# Sheet1.net
KiCad netlist of a schematic drawn in Altium Designer
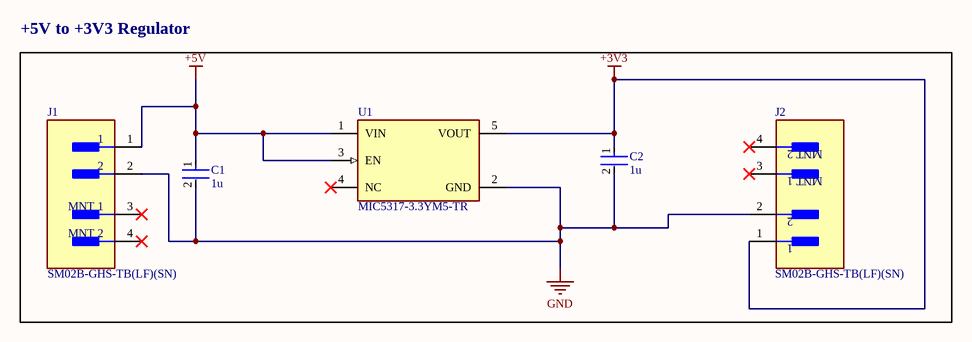
[diagram p0: Sheet1.SchDoc]

(export (version "E")
  (design (tool "Eeschema 10.0.6"))
  (components
    (comp (ref "C1")
      (value "1u")
      (footprint "FP-CC0805-0_85-MFG")
      (description "CAP CER 1UF 10V X7R 0805")
      (fields
        (field (name "MANUFACTURER") "Yageo")
        (field (name "OCTOPART") "https://octopart.com/cc0805kkx7r6bb105-yageo-42522859")
      )
      (libsource (lib "Altium Content Vault") (part "11868f565c42a9108669ba33697ecf6"))
    )
    (comp (ref "C2")
      (value "1u")
      (footprint "FP-CC0805-0_85-MFG")
      (description "CAP CER 1UF 10V X7R 0805")
      (fields
        (field (name "MANUFACTURER") "Yageo")
        (field (name "OCTOPART") "https://octopart.com/cc0805kkx7r6bb105-yageo-42522859")
      )
      (libsource (lib "Altium Content Vault") (part "11868f565c42a9108669ba33697ecf6"))
    )
    (comp (ref "J1")
      (value "SM02B-GHS-TB(LF)(SN)")
      (footprint "FP-SM02B-GHS-TB_LF_SN-MFG")
      (description "CONN HEADER SMD R/A 2POS 1.25MM")
      (libsource (lib "Altium Content Vault") (part "56ec3178a87b3978bdc1b3682cd516a"))
    )
    (comp (ref "J2")
      (value "SM02B-GHS-TB(LF)(SN)")
      (footprint "FP-SM02B-GHS-TB_LF_SN-MFG")
      (description "CONN HEADER SMD R/A 2POS 1.25MM")
      (libsource (lib "") (part "56ec3178a87b3978bdc1b3682cd516a_1"))
    )
    (comp (ref "U1")
      (value "MIC5317-3.3YM5-TR")
      (footprint "FP-SOT23-5LD-PL-1-MFG")
      (description "IC REG LINEAR 3.3V 150MA SOT23-5")
      (libsource (lib "Altium Content Vault") (part "0a093dae7315cdc977fd108dde87457"))
    )
  )
  (nets
    (net (code "1") (name "+3V3") (class "Default")
      (node (ref "C2") (pin "1") (pinfunction "1_1") (pintype "passive"))
      (node (ref "J2") (pin "1") (pinfunction "1_1") (pintype "passive"))
      (node (ref "U1") (pin "5") (pinfunction "VOUT_5") (pintype "power_in"))
    )
    (net (code "2") (name "+5V") (class "Default")
      (node (ref "C1") (pin "1") (pinfunction "1_1") (pintype "passive"))
      (node (ref "J1") (pin "1") (pinfunction "1_1") (pintype "passive"))
      (node (ref "U1") (pin "1") (pinfunction "VIN_1") (pintype "power_in"))
      (node (ref "U1") (pin "3") (pinfunction "EN_3") (pintype "input"))
    )
    (net (code "3") (name "GND") (class "Default")
      (node (ref "C1") (pin "2") (pinfunction "2_2") (pintype "passive"))
      (node (ref "C2") (pin "2") (pinfunction "2_2") (pintype "passive"))
      (node (ref "J1") (pin "2") (pinfunction "2_2") (pintype "passive"))
      (node (ref "J2") (pin "2") (pinfunction "2_2") (pintype "passive"))
      (node (ref "U1") (pin "2") (pinfunction "GND_2") (pintype "power_in"))
    )
    (net (code "4") (name "unconnected-(J1-MNT_1-Pad3)") (class "Default")
      (node (ref "J1") (pin "3") (pinfunction "MNT_1_3") (pintype "passive+no_connect"))
    )
    (net (code "5") (name "unconnected-(J1-MNT_2-Pad4)") (class "Default")
      (node (ref "J1") (pin "4") (pinfunction "MNT_2_4") (pintype "passive+no_connect"))
    )
    (net (code "6") (name "unconnected-(J2-MNT_1-Pad3)") (class "Default")
      (node (ref "J2") (pin "3") (pinfunction "MNT_1_3") (pintype "passive+no_connect"))
    )
    (net (code "7") (name "unconnected-(J2-MNT_2-Pad4)") (class "Default")
      (node (ref "J2") (pin "4") (pinfunction "MNT_2_4") (pintype "passive+no_connect"))
    )
    (net (code "8") (name "unconnected-(U1-NC-Pad4)") (class "Default")
      (node (ref "U1") (pin "4") (pinfunction "NC_4") (pintype "passive+no_connect"))
    )
  )
)
